# photo.net
KiCad netlist of a schematic drawn in EAGLE
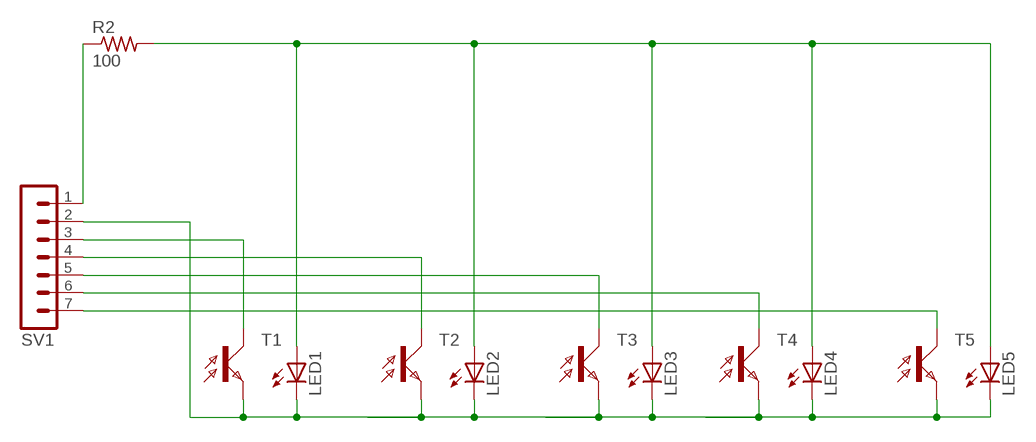
[diagram p0: schematic, sheet 1]

(export (version "E")
  (design (tool "Eeschema 10.0.6"))
  (components
    (comp (ref "LED1")
      (value "LED3MM")
      (footprint "eagle-import:LED3MM")
      (libsource (lib "eagle-import") (part "LED3MM"))
    )
    (comp (ref "LED2")
      (value "LED3MM")
      (footprint "eagle-import:LED3MM")
      (libsource (lib "eagle-import") (part "LED3MM"))
    )
    (comp (ref "LED3")
      (value "LED3MM")
      (footprint "eagle-import:LED3MM")
      (libsource (lib "eagle-import") (part "LED3MM"))
    )
    (comp (ref "LED4")
      (value "LED3MM")
      (footprint "eagle-import:LED3MM")
      (libsource (lib "eagle-import") (part "LED3MM"))
    )
    (comp (ref "LED5")
      (value "LED3MM")
      (footprint "eagle-import:LED3MM")
      (libsource (lib "eagle-import") (part "LED3MM"))
    )
    (comp (ref "R2")
      (value "100")
      (footprint "eagle-import:0204_7")
      (libsource (lib "eagle-import") (part "R-US_0204/7"))
    )
    (comp (ref "SV1")
      (value "MA07-1")
      (footprint "eagle-import:MA07-1")
      (libsource (lib "eagle-import") (part "MA07-1"))
    )
    (comp (ref "T1")
      (value "LPT80A")
      (footprint "eagle-import:LPT80A")
      (libsource (lib "eagle-import") (part "LPT80A"))
    )
    (comp (ref "T2")
      (value "LPT80A")
      (footprint "eagle-import:LPT80A")
      (libsource (lib "eagle-import") (part "LPT80A"))
    )
    (comp (ref "T3")
      (value "LPT80A")
      (footprint "eagle-import:LPT80A")
      (libsource (lib "eagle-import") (part "LPT80A"))
    )
    (comp (ref "T4")
      (value "LPT80A")
      (footprint "eagle-import:LPT80A")
      (libsource (lib "eagle-import") (part "LPT80A"))
    )
    (comp (ref "T5")
      (value "LPT80A")
      (footprint "eagle-import:LPT80A")
      (libsource (lib "eagle-import") (part "LPT80A"))
    )
  )
  (nets
    (net (code "1") (name "Net-(LED1-C)") (class "Default")
      (node (ref "LED1") (pin "K") (pinfunction "C_K") (pintype "passive"))
      (node (ref "LED2") (pin "K") (pinfunction "C_K") (pintype "passive"))
      (node (ref "LED3") (pin "K") (pinfunction "C_K") (pintype "passive"))
      (node (ref "LED4") (pin "K") (pinfunction "C_K") (pintype "passive"))
      (node (ref "LED5") (pin "K") (pinfunction "C_K") (pintype "passive"))
      (node (ref "SV1") (pin "2") (pinfunction "2_2") (pintype "passive"))
      (node (ref "T1") (pin "E") (pinfunction "E_E") (pintype "passive"))
      (node (ref "T2") (pin "E") (pinfunction "E_E") (pintype "passive"))
      (node (ref "T3") (pin "E") (pinfunction "E_E") (pintype "passive"))
      (node (ref "T4") (pin "E") (pinfunction "E_E") (pintype "passive"))
      (node (ref "T5") (pin "E") (pinfunction "E_E") (pintype "passive"))
    )
    (net (code "2") (name "Net-(LED1-PadA)") (class "Default")
      (node (ref "LED1") (pin "A") (pinfunction "A_A") (pintype "passive"))
      (node (ref "LED2") (pin "A") (pinfunction "A_A") (pintype "passive"))
      (node (ref "LED3") (pin "A") (pinfunction "A_A") (pintype "passive"))
      (node (ref "LED4") (pin "A") (pinfunction "A_A") (pintype "passive"))
      (node (ref "LED5") (pin "A") (pinfunction "A_A") (pintype "passive"))
      (node (ref "R2") (pin "2") (pinfunction "2_2") (pintype "passive"))
    )
    (net (code "3") (name "Net-(R2-Pad1)") (class "Default")
      (node (ref "R2") (pin "1") (pinfunction "1_1") (pintype "passive"))
      (node (ref "SV1") (pin "1") (pinfunction "1_1") (pintype "passive"))
    )
    (net (code "4") (name "Net-(SV1-Pad3)") (class "Default")
      (node (ref "SV1") (pin "3") (pinfunction "3_3") (pintype "passive"))
      (node (ref "T1") (pin "C") (pinfunction "C_C") (pintype "passive"))
    )
    (net (code "5") (name "Net-(SV1-Pad4)") (class "Default")
      (node (ref "SV1") (pin "4") (pinfunction "4_4") (pintype "passive"))
      (node (ref "T2") (pin "C") (pinfunction "C_C") (pintype "passive"))
    )
    (net (code "6") (name "Net-(SV1-Pad5)") (class "Default")
      (node (ref "SV1") (pin "5") (pinfunction "5_5") (pintype "passive"))
      (node (ref "T3") (pin "C") (pinfunction "C_C") (pintype "passive"))
    )
    (net (code "7") (name "Net-(SV1-Pad6)") (class "Default")
      (node (ref "SV1") (pin "6") (pinfunction "6_6") (pintype "passive"))
      (node (ref "T4") (pin "C") (pinfunction "C_C") (pintype "passive"))
    )
    (net (code "8") (name "Net-(SV1-Pad7)") (class "Default")
      (node (ref "SV1") (pin "7") (pinfunction "7_7") (pintype "passive"))
      (node (ref "T5") (pin "C") (pinfunction "C_C") (pintype "passive"))
    )
  )
)
